# mini_tft_carrier.net
KiCad netlist of a schematic drawn in EAGLE
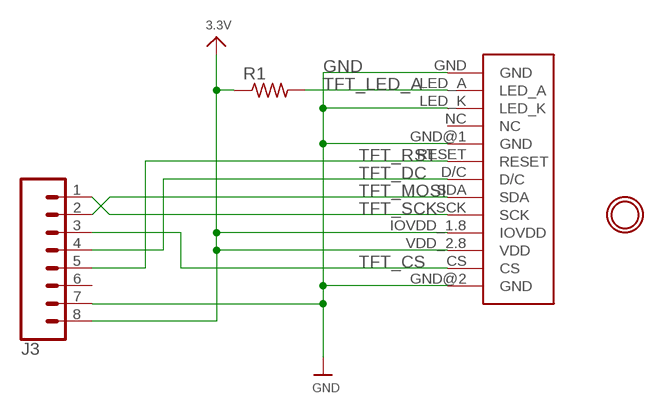
[diagram p0: schematic, sheet 1]

(export (version "E")
  (design (tool "Eeschema 10.0.6"))
  (components
    (comp (ref "J3")
      (value "CONN_08NO_SILK_FEMALE_PTH")
      (footprint "eagle-import:1X08_NO_SILK")
      (libsource (lib "eagle-import") (part "CONN_08NO_SILK_FEMALE_PTH"))
    )
    (comp (ref "R1")
      (value "R-US_R0603")
      (footprint "eagle-import:R0603")
      (libsource (lib "eagle-import") (part "R-US_R0603"))
    )
    (comp (ref "U$1")
      (value "MICRO_TFT")
      (footprint "eagle-import:MICRO_TFT")
      (libsource (lib "eagle-import") (part "MICRO_TFT"))
    )
    (comp (ref "U$2")
      (value "MOUNTINGHOLE2.5")
      (footprint "eagle-import:MOUNTINGHOLE_2.5_PLATED")
      (libsource (lib "eagle-import") (part "MOUNTINGHOLE2.5"))
    )
  )
  (nets
    (net (code "1") (name "/TFT_CS") (class "Default")
      (node (ref "J3") (pin "3") (pinfunction "3_3") (pintype "passive"))
      (node (ref "U$1") (pin "CS") (pinfunction "CS_CS") (pintype "bidirectional"))
    )
    (net (code "2") (name "/TFT_DC") (class "Default")
      (node (ref "J3") (pin "4") (pinfunction "4_4") (pintype "passive"))
      (node (ref "U$1") (pin "D/C") (pinfunction "D/C_D/C") (pintype "bidirectional"))
    )
    (net (code "3") (name "/TFT_LED_A") (class "Default")
      (node (ref "R1") (pin "2") (pinfunction "2_2") (pintype "passive"))
      (node (ref "U$1") (pin "LED_A") (pinfunction "LED_A_LED_A") (pintype "bidirectional"))
    )
    (net (code "4") (name "/TFT_MOSI") (class "Default")
      (node (ref "J3") (pin "2") (pinfunction "2_2") (pintype "passive"))
      (node (ref "U$1") (pin "SDA") (pinfunction "SDA_SDA") (pintype "bidirectional"))
    )
    (net (code "5") (name "/TFT_RST") (class "Default")
      (node (ref "J3") (pin "5") (pinfunction "5_5") (pintype "passive"))
      (node (ref "U$1") (pin "RESET") (pinfunction "RESET_RESET") (pintype "bidirectional"))
    )
    (net (code "6") (name "/TFT_SCK") (class "Default")
      (node (ref "J3") (pin "1") (pinfunction "1_1") (pintype "passive"))
      (node (ref "U$1") (pin "SCK") (pinfunction "SCK_SCK") (pintype "bidirectional"))
    )
    (net (code "7") (name "3.3V") (class "Default")
      (node (ref "J3") (pin "8") (pinfunction "8_8") (pintype "passive"))
      (node (ref "R1") (pin "1") (pinfunction "1_1") (pintype "passive"))
      (node (ref "U$1") (pin "IOVDD_1.8") (pinfunction "IOVDD_IOVDD_1.8") (pintype "bidirectional"))
      (node (ref "U$1") (pin "VDD_2.8") (pinfunction "VDD_VDD_2.8") (pintype "bidirectional"))
    )
    (net (code "8") (name "GND") (class "Default")
      (node (ref "J3") (pin "7") (pinfunction "7_7") (pintype "passive"))
      (node (ref "U$1") (pin "GND") (pinfunction "GND_GND") (pintype "bidirectional"))
      (node (ref "U$1") (pin "GND@1") (pinfunction "GND_GND@1") (pintype "bidirectional"))
      (node (ref "U$1") (pin "GND@2") (pinfunction "GND_GND@2") (pintype "bidirectional"))
      (node (ref "U$1") (pin "LED_K") (pinfunction "LED_K_LED_K") (pintype "bidirectional"))
    )
    (net (code "9") (name "unconnected-(J3-Pad6)") (class "Default")
      (node (ref "J3") (pin "6") (pinfunction "6_6") (pintype "passive"))
    )
    (net (code "10") (name "unconnected-(U$1-PadNC)") (class "Default")
      (node (ref "U$1") (pin "NC") (pinfunction "NC_NC") (pintype "bidirectional"))
    )
  )
)
